# MP5x16_V1_0.net
KiCad netlist of a schematic drawn in EAGLE
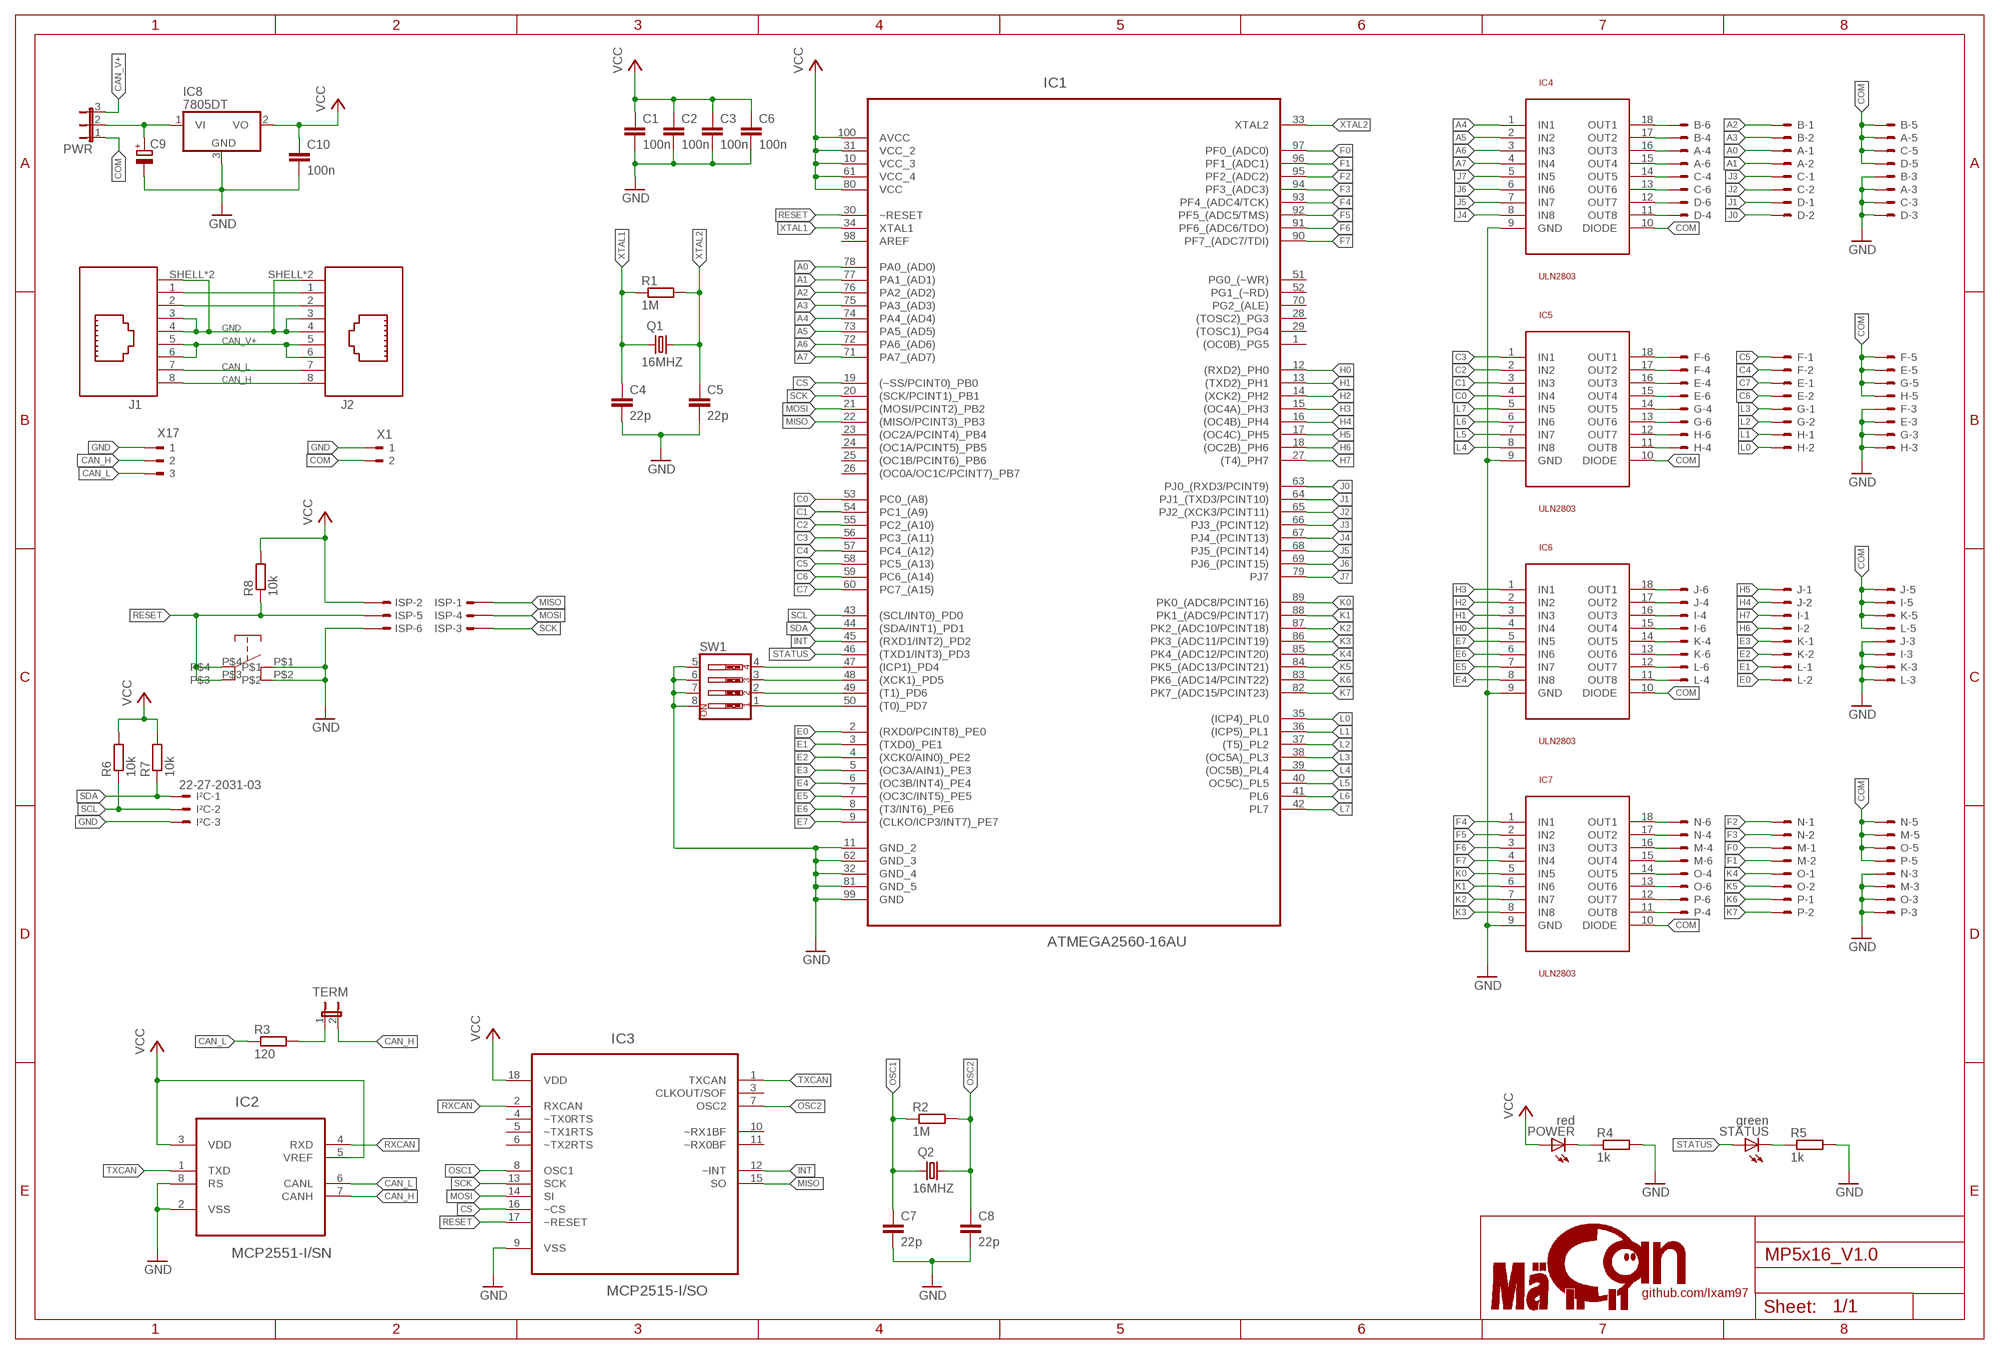
[diagram p0: schematic, sheet 1]

(export (version "E")
  (design (tool "Eeschema 10.0.6"))
  (components
    (comp (ref "A")
      (value "22-27-2061-06")
      (footprint "eagle-import:6410-06")
      (fields (field (name "MF") "MOLEX"))
      (libsource (lib "eagle-import") (part "22-?-0627-2061"))
    )
    (comp (ref "B")
      (value "22-27-2061-06")
      (footprint "eagle-import:6410-06")
      (fields (field (name "MF") "MOLEX"))
      (libsource (lib "eagle-import") (part "22-?-0627-2061"))
    )
    (comp (ref "C")
      (value "22-27-2061-06")
      (footprint "eagle-import:6410-06")
      (fields (field (name "MF") "MOLEX"))
      (libsource (lib "eagle-import") (part "22-?-0627-2061"))
    )
    (comp (ref "C1")
      (value "100n")
      (footprint "eagle-import:C0402")
      (libsource (lib "eagle-import") (part "C-EUC0402"))
    )
    (comp (ref "C2")
      (value "100n")
      (footprint "eagle-import:C0402")
      (libsource (lib "eagle-import") (part "C-EUC0402"))
    )
    (comp (ref "C3")
      (value "100n")
      (footprint "eagle-import:C0402")
      (libsource (lib "eagle-import") (part "C-EUC0402"))
    )
    (comp (ref "C4")
      (value "22p")
      (footprint "eagle-import:C0402")
      (libsource (lib "eagle-import") (part "C-EUC0402"))
    )
    (comp (ref "C5")
      (value "22p")
      (footprint "eagle-import:C0402")
      (libsource (lib "eagle-import") (part "C-EUC0402"))
    )
    (comp (ref "C6")
      (value "100n")
      (footprint "eagle-import:C0402")
      (libsource (lib "eagle-import") (part "C-EUC0402"))
    )
    (comp (ref "C7")
      (value "22p")
      (footprint "eagle-import:C0402")
      (libsource (lib "eagle-import") (part "C-EUC0402"))
    )
    (comp (ref "C8")
      (value "22p")
      (footprint "eagle-import:C0402")
      (libsource (lib "eagle-import") (part "C-EUC0402"))
    )
    (comp (ref "C9")
      (value "CPOL-EUCT3216")
      (footprint "eagle-import:CT3216")
      (libsource (lib "eagle-import") (part "CPOL-EUCT3216"))
    )
    (comp (ref "C10")
      (value "100n")
      (footprint "eagle-import:C0402")
      (libsource (lib "eagle-import") (part "C-EUC0402"))
    )
    (comp (ref "D")
      (value "22-27-2061-06")
      (footprint "eagle-import:6410-06")
      (fields (field (name "MF") "MOLEX"))
      (libsource (lib "eagle-import") (part "22-?-0627-2061"))
    )
    (comp (ref "E")
      (value "22-27-2061-06")
      (footprint "eagle-import:6410-06")
      (fields (field (name "MF") "MOLEX"))
      (libsource (lib "eagle-import") (part "22-?-0627-2061"))
    )
    (comp (ref "F")
      (value "22-27-2061-06")
      (footprint "eagle-import:6410-06")
      (fields (field (name "MF") "MOLEX"))
      (libsource (lib "eagle-import") (part "22-?-0627-2061"))
    )
    (comp (ref "G")
      (value "22-27-2061-06")
      (footprint "eagle-import:6410-06")
      (fields (field (name "MF") "MOLEX"))
      (libsource (lib "eagle-import") (part "22-?-0627-2061"))
    )
    (comp (ref "H")
      (value "22-27-2061-06")
      (footprint "eagle-import:6410-06")
      (fields (field (name "MF") "MOLEX"))
      (libsource (lib "eagle-import") (part "22-?-0627-2061"))
    )
    (comp (ref "I")
      (value "22-27-2061-06")
      (footprint "eagle-import:6410-06")
      (fields (field (name "MF") "MOLEX"))
      (libsource (lib "eagle-import") (part "22-?-0627-2061"))
    )
    (comp (ref "IC1")
      (value "ATMEGA2560-16AU")
      (footprint "eagle-import:QFP50P1600X1600X120-100N")
      (fields (field (name "MF") "Microchip"))
      (libsource (lib "eagle-import") (part "ATMEGA2560-16AU"))
    )
    (comp (ref "IC2")
      (value "MCP2551-I/SN")
      (footprint "eagle-import:SOIC127P600X175-8N")
      (libsource (lib "eagle-import") (part "MCP2551-I/SN"))
    )
    (comp (ref "IC3")
      (value "MCP2515-I/SO")
      (footprint "eagle-import:SOIC127P1034X264-18N")
      (libsource (lib "eagle-import") (part "MCP2515-I/SO"))
    )
    (comp (ref "IC4")
      (value "ULN2803")
      (footprint "eagle-import:SO18L")
      (libsource (lib "eagle-import") (part "ULN2803"))
    )
    (comp (ref "IC5")
      (value "ULN2803")
      (footprint "eagle-import:SO18L")
      (libsource (lib "eagle-import") (part "ULN2803"))
    )
    (comp (ref "IC6")
      (value "ULN2803")
      (footprint "eagle-import:SO18L")
      (libsource (lib "eagle-import") (part "ULN2803"))
    )
    (comp (ref "IC7")
      (value "ULN2803")
      (footprint "eagle-import:SO18L")
      (libsource (lib "eagle-import") (part "ULN2803"))
    )
    (comp (ref "IC8")
      (value "7805DT")
      (footprint "eagle-import:TO252")
      (libsource (lib "eagle-import") (part "78DT05"))
    )
    (comp (ref "ISP")
      (value "057-006-1")
      (footprint "eagle-import:057-006-1")
      (libsource (lib "eagle-import") (part "057-006-1"))
    )
    (comp (ref "I²C")
      (value "22-27-2031-03")
      (footprint "eagle-import:6410-03")
      (fields (field (name "MF") "MOLEX"))
      (libsource (lib "eagle-import") (part "22-?-0327-2031"))
    )
    (comp (ref "J")
      (value "22-27-2061-06")
      (footprint "eagle-import:6410-06")
      (fields (field (name "MF") "MOLEX"))
      (libsource (lib "eagle-import") (part "22-?-0627-2061"))
    )
    (comp (ref "J1")
      (value "615008140421")
      (footprint "eagle-import:615008140421")
      (libsource (lib "eagle-import") (part "615008140421"))
    )
    (comp (ref "J2")
      (value "615008140421")
      (footprint "eagle-import:615008140421")
      (libsource (lib "eagle-import") (part "615008140421"))
    )
    (comp (ref "K")
      (value "22-27-2061-06")
      (footprint "eagle-import:6410-06")
      (fields (field (name "MF") "MOLEX"))
      (libsource (lib "eagle-import") (part "22-?-0627-2061"))
    )
    (comp (ref "L")
      (value "22-27-2061-06")
      (footprint "eagle-import:6410-06")
      (fields (field (name "MF") "MOLEX"))
      (libsource (lib "eagle-import") (part "22-?-0627-2061"))
    )
    (comp (ref "M")
      (value "22-27-2061-06")
      (footprint "eagle-import:6410-06")
      (fields (field (name "MF") "MOLEX"))
      (libsource (lib "eagle-import") (part "22-?-0627-2061"))
    )
    (comp (ref "N")
      (value "22-27-2061-06")
      (footprint "eagle-import:6410-06")
      (fields (field (name "MF") "MOLEX"))
      (libsource (lib "eagle-import") (part "22-?-0627-2061"))
    )
    (comp (ref "O")
      (value "22-27-2061-06")
      (footprint "eagle-import:6410-06")
      (fields (field (name "MF") "MOLEX"))
      (libsource (lib "eagle-import") (part "22-?-0627-2061"))
    )
    (comp (ref "P")
      (value "22-27-2061-06")
      (footprint "eagle-import:6410-06")
      (fields (field (name "MF") "MOLEX"))
      (libsource (lib "eagle-import") (part "22-?-0627-2061"))
    )
    (comp (ref "POWER")
      (value "red")
      (footprint "eagle-import:CHIP-LED0805")
      (libsource (lib "eagle-import") (part "LEDCHIP-LED0805"))
    )
    (comp (ref "PWR")
      (value "JP2E")
      (footprint "eagle-import:JP2")
      (libsource (lib "eagle-import") (part "JP2E"))
    )
    (comp (ref "Q1")
      (value "16MHZ")
      (footprint "eagle-import:3.2X2.5_KX-7")
      (libsource (lib "eagle-import") (part "KX-7"))
    )
    (comp (ref "Q2")
      (value "16MHZ")
      (footprint "eagle-import:3.2X2.5_KX-7")
      (libsource (lib "eagle-import") (part "KX-7"))
    )
    (comp (ref "R1")
      (value "1M")
      (footprint "eagle-import:R0402")
      (libsource (lib "eagle-import") (part "R-EU_R0402"))
    )
    (comp (ref "R2")
      (value "1M")
      (footprint "eagle-import:R0402")
      (libsource (lib "eagle-import") (part "R-EU_R0402"))
    )
    (comp (ref "R3")
      (value "120")
      (footprint "eagle-import:R0402")
      (libsource (lib "eagle-import") (part "R-EU_R0402"))
    )
    (comp (ref "R4")
      (value "1k")
      (footprint "eagle-import:R0402")
      (libsource (lib "eagle-import") (part "R-EU_R0402"))
    )
    (comp (ref "R5")
      (value "1k")
      (footprint "eagle-import:R0402")
      (libsource (lib "eagle-import") (part "R-EU_R0402"))
    )
    (comp (ref "R6")
      (value "10k")
      (footprint "eagle-import:R0402")
      (libsource (lib "eagle-import") (part "R-EU_R0402"))
    )
    (comp (ref "R7")
      (value "10k")
      (footprint "eagle-import:R0402")
      (libsource (lib "eagle-import") (part "R-EU_R0402"))
    )
    (comp (ref "R8")
      (value "10k")
      (footprint "eagle-import:R0402")
      (libsource (lib "eagle-import") (part "R-EU_R0402"))
    )
    (comp (ref "STATUS")
      (value "green")
      (footprint "eagle-import:CHIP-LED0805")
      (libsource (lib "eagle-import") (part "LEDCHIP-LED0805"))
    )
    (comp (ref "SW1")
      (value "SW_DIP-4")
      (footprint "eagle-import:EDG-04")
      (libsource (lib "eagle-import") (part "SW_DIP-4"))
    )
    (comp (ref "TERM")
      (value "JP1E")
      (footprint "eagle-import:JP1")
      (libsource (lib "eagle-import") (part "JP1E"))
    )
    (comp (ref "U$1")
      (value "LOGO")
      (footprint "eagle-import:LOGO")
      (libsource (lib "eagle-import") (part "LOGO"))
    )
    (comp (ref "U$15")
      (value "BUTTON_JLC")
      (footprint "eagle-import:BUTTON")
      (libsource (lib "eagle-import") (part "BUTTON_JLC"))
    )
    (comp (ref "X1")
      (value "180-2")
      (footprint "eagle-import:180-2")
      (libsource (lib "eagle-import") (part "180-2"))
    )
    (comp (ref "X17")
      (value "180-3")
      (footprint "eagle-import:180-3")
      (libsource (lib "eagle-import") (part "180-3"))
    )
  )
  (nets
    (net (code "1") (name "A0") (class "Default")
      (node (ref "A") (pin "1") (pinfunction "S_1") (pintype "passive"))
      (node (ref "IC1") (pin "78") (pinfunction "PA0_(AD0)_78") (pintype "bidirectional"))
    )
    (net (code "2") (name "A1") (class "Default")
      (node (ref "A") (pin "2") (pinfunction "S_2") (pintype "passive"))
      (node (ref "IC1") (pin "77") (pinfunction "PA1_(AD1)_77") (pintype "bidirectional"))
    )
    (net (code "3") (name "A2") (class "Default")
      (node (ref "B") (pin "1") (pinfunction "S_1") (pintype "passive"))
      (node (ref "IC1") (pin "76") (pinfunction "PA2_(AD2)_76") (pintype "bidirectional"))
    )
    (net (code "4") (name "A3") (class "Default")
      (node (ref "B") (pin "2") (pinfunction "S_2") (pintype "passive"))
      (node (ref "IC1") (pin "75") (pinfunction "PA3_(AD3)_75") (pintype "bidirectional"))
    )
    (net (code "5") (name "A4") (class "Default")
      (node (ref "IC1") (pin "74") (pinfunction "PA4_(AD4)_74") (pintype "bidirectional"))
      (node (ref "IC4") (pin "1") (pinfunction "IN1_1") (pintype "input"))
    )
    (net (code "6") (name "A5") (class "Default")
      (node (ref "IC1") (pin "73") (pinfunction "PA5_(AD5)_73") (pintype "bidirectional"))
      (node (ref "IC4") (pin "2") (pinfunction "IN2_2") (pintype "input"))
    )
    (net (code "7") (name "A6") (class "Default")
      (node (ref "IC1") (pin "72") (pinfunction "PA6_(AD6)_72") (pintype "bidirectional"))
      (node (ref "IC4") (pin "3") (pinfunction "IN3_3") (pintype "input"))
    )
    (net (code "8") (name "A7") (class "Default")
      (node (ref "IC1") (pin "71") (pinfunction "PA7_(AD7)_71") (pintype "bidirectional"))
      (node (ref "IC4") (pin "4") (pinfunction "IN4_4") (pintype "input"))
    )
    (net (code "9") (name "C0") (class "Default")
      (node (ref "IC1") (pin "53") (pinfunction "PC0_(A8)_53") (pintype "bidirectional"))
      (node (ref "IC5") (pin "4") (pinfunction "IN4_4") (pintype "input"))
    )
    (net (code "10") (name "C1") (class "Default")
      (node (ref "IC1") (pin "54") (pinfunction "PC1_(A9)_54") (pintype "bidirectional"))
      (node (ref "IC5") (pin "3") (pinfunction "IN3_3") (pintype "input"))
    )
    (net (code "11") (name "C2") (class "Default")
      (node (ref "IC1") (pin "55") (pinfunction "PC2_(A10)_55") (pintype "bidirectional"))
      (node (ref "IC5") (pin "2") (pinfunction "IN2_2") (pintype "input"))
    )
    (net (code "12") (name "C3") (class "Default")
      (node (ref "IC1") (pin "56") (pinfunction "PC3_(A11)_56") (pintype "bidirectional"))
      (node (ref "IC5") (pin "1") (pinfunction "IN1_1") (pintype "input"))
    )
    (net (code "13") (name "C4") (class "Default")
      (node (ref "F") (pin "2") (pinfunction "S_2") (pintype "passive"))
      (node (ref "IC1") (pin "57") (pinfunction "PC4_(A12)_57") (pintype "bidirectional"))
    )
    (net (code "14") (name "C5") (class "Default")
      (node (ref "F") (pin "1") (pinfunction "S_1") (pintype "passive"))
      (node (ref "IC1") (pin "58") (pinfunction "PC5_(A13)_58") (pintype "bidirectional"))
    )
    (net (code "15") (name "C6") (class "Default")
      (node (ref "E") (pin "2") (pinfunction "S_2") (pintype "passive"))
      (node (ref "IC1") (pin "59") (pinfunction "PC6_(A14)_59") (pintype "bidirectional"))
    )
    (net (code "16") (name "C7") (class "Default")
      (node (ref "E") (pin "1") (pinfunction "S_1") (pintype "passive"))
      (node (ref "IC1") (pin "60") (pinfunction "PC7_(A15)_60") (pintype "bidirectional"))
    )
    (net (code "17") (name "CAN_H") (class "Default")
      (node (ref "IC2") (pin "7") (pinfunction "CANH_7") (pintype "bidirectional"))
      (node (ref "J1") (pin "8") (pinfunction "8_8") (pintype "passive"))
      (node (ref "J2") (pin "8") (pinfunction "8_8") (pintype "passive"))
      (node (ref "TERM") (pin "2") (pinfunction "2_2") (pintype "passive"))
      (node (ref "X17") (pin "2") (pinfunction "2_2") (pintype "passive"))
    )
    (net (code "18") (name "CAN_L") (class "Default")
      (node (ref "IC2") (pin "6") (pinfunction "CANL_6") (pintype "bidirectional"))
      (node (ref "J1") (pin "7") (pinfunction "7_7") (pintype "passive"))
      (node (ref "J2") (pin "7") (pinfunction "7_7") (pintype "passive"))
      (node (ref "R3") (pin "1") (pinfunction "1_1") (pintype "passive"))
      (node (ref "X17") (pin "3") (pinfunction "3_3") (pintype "passive"))
    )
    (net (code "19") (name "CAN_V+") (class "Default")
      (node (ref "J1") (pin "5") (pinfunction "5_5") (pintype "passive"))
      (node (ref "J1") (pin "6") (pinfunction "6_6") (pintype "passive"))
      (node (ref "J2") (pin "5") (pinfunction "5_5") (pintype "passive"))
      (node (ref "J2") (pin "6") (pinfunction "6_6") (pintype "passive"))
      (node (ref "PWR") (pin "3") (pinfunction "3_3") (pintype "passive"))
    )
    (net (code "20") (name "COM") (class "Default")
      (node (ref "A") (pin "5") (pinfunction "S_5") (pintype "passive"))
      (node (ref "B") (pin "5") (pinfunction "S_5") (pintype "passive"))
      (node (ref "C") (pin "5") (pinfunction "S_5") (pintype "passive"))
      (node (ref "D") (pin "5") (pinfunction "S_5") (pintype "passive"))
      (node (ref "E") (pin "5") (pinfunction "S_5") (pintype "passive"))
      (node (ref "F") (pin "5") (pinfunction "S_5") (pintype "passive"))
      (node (ref "G") (pin "5") (pinfunction "S_5") (pintype "passive"))
      (node (ref "H") (pin "5") (pinfunction "S_5") (pintype "passive"))
      (node (ref "I") (pin "5") (pinfunction "S_5") (pintype "passive"))
      (node (ref "IC4") (pin "10") (pinfunction "DIODE_10") (pintype "power_in"))
      (node (ref "IC5") (pin "10") (pinfunction "DIODE_10") (pintype "power_in"))
      (node (ref "IC6") (pin "10") (pinfunction "DIODE_10") (pintype "power_in"))
      (node (ref "IC7") (pin "10") (pinfunction "DIODE_10") (pintype "power_in"))
      (node (ref "J") (pin "5") (pinfunction "S_5") (pintype "passive"))
      (node (ref "K") (pin "5") (pinfunction "S_5") (pintype "passive"))
      (node (ref "L") (pin "5") (pinfunction "S_5") (pintype "passive"))
      (node (ref "M") (pin "5") (pinfunction "S_5") (pintype "passive"))
      (node (ref "N") (pin "5") (pinfunction "S_5") (pintype "passive"))
      (node (ref "O") (pin "5") (pinfunction "S_5") (pintype "passive"))
      (node (ref "P") (pin "5") (pinfunction "S_5") (pintype "passive"))
      (node (ref "PWR") (pin "1") (pinfunction "1_1") (pintype "passive"))
      (node (ref "X1") (pin "2") (pinfunction "2_2") (pintype "passive"))
    )
    (net (code "21") (name "CS") (class "Default")
      (node (ref "IC1") (pin "19") (pinfunction "(~{SS/PCINT0})_PB0_19") (pintype "bidirectional"))
      (node (ref "IC3") (pin "16") (pinfunction "~{CS}_16") (pintype "input"))
    )
    (net (code "22") (name "E0") (class "Default")
      (node (ref "IC1") (pin "2") (pinfunction "(RXD0/PCINT8)_PE0_2") (pintype "bidirectional"))
      (node (ref "L") (pin "2") (pinfunction "S_2") (pintype "passive"))
    )
    (net (code "23") (name "E1") (class "Default")
      (node (ref "IC1") (pin "3") (pinfunction "(TXD0)_PE1_3") (pintype "bidirectional"))
      (node (ref "L") (pin "1") (pinfunction "S_1") (pintype "passive"))
    )
    (net (code "24") (name "E2") (class "Default")
      (node (ref "IC1") (pin "4") (pinfunction "(XCK0/AIN0)_PE2_4") (pintype "bidirectional"))
      (node (ref "K") (pin "2") (pinfunction "S_2") (pintype "passive"))
    )
    (net (code "25") (name "E3") (class "Default")
      (node (ref "IC1") (pin "5") (pinfunction "(OC3A/AIN1)_PE3_5") (pintype "bidirectional"))
      (node (ref "K") (pin "1") (pinfunction "S_1") (pintype "passive"))
    )
    (net (code "26") (name "E4") (class "Default")
      (node (ref "IC1") (pin "6") (pinfunction "(OC3B/INT4)_PE4_6") (pintype "bidirectional"))
      (node (ref "IC6") (pin "8") (pinfunction "IN8_8") (pintype "input"))
    )
    (net (code "27") (name "E5") (class "Default")
      (node (ref "IC1") (pin "7") (pinfunction "(OC3C/INT5)_PE5_7") (pintype "bidirectional"))
      (node (ref "IC6") (pin "7") (pinfunction "IN7_7") (pintype "input"))
    )
    (net (code "28") (name "E6") (class "Default")
      (node (ref "IC1") (pin "8") (pinfunction "(T3/INT6)_PE6_8") (pintype "bidirectional"))
      (node (ref "IC6") (pin "6") (pinfunction "IN6_6") (pintype "input"))
    )
    (net (code "29") (name "E7") (class "Default")
      (node (ref "IC1") (pin "9") (pinfunction "(CLKO/ICP3/INT7)_PE7_9") (pintype "bidirectional"))
      (node (ref "IC6") (pin "5") (pinfunction "IN5_5") (pintype "input"))
    )
    (net (code "30") (name "F0") (class "Default")
      (node (ref "IC1") (pin "97") (pinfunction "PF0_(ADC0)_97") (pintype "bidirectional"))
      (node (ref "M") (pin "1") (pinfunction "S_1") (pintype "passive"))
    )
    (net (code "31") (name "F1") (class "Default")
      (node (ref "IC1") (pin "96") (pinfunction "PF1_(ADC1)_96") (pintype "bidirectional"))
      (node (ref "M") (pin "2") (pinfunction "S_2") (pintype "passive"))
    )
    (net (code "32") (name "F2") (class "Default")
      (node (ref "IC1") (pin "95") (pinfunction "PF2_(ADC2)_95") (pintype "bidirectional"))
      (node (ref "N") (pin "1") (pinfunction "S_1") (pintype "passive"))
    )
    (net (code "33") (name "F3") (class "Default")
      (node (ref "IC1") (pin "94") (pinfunction "PF3_(ADC3)_94") (pintype "bidirectional"))
      (node (ref "N") (pin "2") (pinfunction "S_2") (pintype "passive"))
    )
    (net (code "34") (name "F4") (class "Default")
      (node (ref "IC1") (pin "93") (pinfunction "PF4_(ADC4/TCK)_93") (pintype "bidirectional"))
      (node (ref "IC7") (pin "1") (pinfunction "IN1_1") (pintype "input"))
    )
    (net (code "35") (name "F5") (class "Default")
      (node (ref "IC1") (pin "92") (pinfunction "PF5_(ADC5/TMS)_92") (pintype "bidirectional"))
      (node (ref "IC7") (pin "2") (pinfunction "IN2_2") (pintype "input"))
    )
    (net (code "36") (name "F6") (class "Default")
      (node (ref "IC1") (pin "91") (pinfunction "PF6_(ADC6/TDO)_91") (pintype "bidirectional"))
      (node (ref "IC7") (pin "3") (pinfunction "IN3_3") (pintype "input"))
    )
    (net (code "37") (name "F7") (class "Default")
      (node (ref "IC1") (pin "90") (pinfunction "PF7_(ADC7/TDI)_90") (pintype "bidirectional"))
      (node (ref "IC7") (pin "4") (pinfunction "IN4_4") (pintype "input"))
    )
    (net (code "38") (name "GND") (class "Default")
      (node (ref "A") (pin "3") (pinfunction "S_3") (pintype "passive"))
      (node (ref "B") (pin "3") (pinfunction "S_3") (pintype "passive"))
      (node (ref "C") (pin "3") (pinfunction "S_3") (pintype "passive"))
      (node (ref "C1") (pin "2") (pinfunction "2_2") (pintype "passive"))
      (node (ref "C10") (pin "2") (pinfunction "2_2") (pintype "passive"))
      (node (ref "C2") (pin "2") (pinfunction "2_2") (pintype "passive"))
      (node (ref "C3") (pin "2") (pinfunction "2_2") (pintype "passive"))
      (node (ref "C4") (pin "2") (pinfunction "2_2") (pintype "passive"))
      (node (ref "C5") (pin "2") (pinfunction "2_2") (pintype "passive"))
      (node (ref "C6") (pin "2") (pinfunction "2_2") (pintype "passive"))
      (node (ref "C7") (pin "2") (pinfunction "2_2") (pintype "passive"))
      (node (ref "C8") (pin "2") (pinfunction "2_2") (pintype "passive"))
      (node (ref "C9") (pin "-") (pinfunction "-_-") (pintype "passive"))
      (node (ref "D") (pin "3") (pinfunction "S_3") (pintype "passive"))
      (node (ref "E") (pin "3") (pinfunction "S_3") (pintype "passive"))
      (node (ref "F") (pin "3") (pinfunction "S_3") (pintype "passive"))
      (node (ref "G") (pin "3") (pinfunction "S_3") (pintype "passive"))
      (node (ref "H") (pin "3") (pinfunction "S_3") (pintype "passive"))
      (node (ref "I") (pin "3") (pinfunction "S_3") (pintype "passive"))
      (node (ref "IC1") (pin "11") (pinfunction "GND_2_11") (pintype "passive"))
      (node (ref "IC1") (pin "32") (pinfunction "GND_4_32") (pintype "passive"))
      (node (ref "IC1") (pin "62") (pinfunction "GND_3_62") (pintype "passive"))
      (node (ref "IC1") (pin "81") (pinfunction "GND_5_81") (pintype "passive"))
      (node (ref "IC1") (pin "99") (pinfunction "GND_99") (pintype "passive"))
      (node (ref "IC2") (pin "2") (pinfunction "VSS_2") (pintype "passive"))
      (node (ref "IC2") (pin "8") (pinfunction "RS_8") (pintype "input"))
      (node (ref "IC3") (pin "9") (pinfunction "VSS_9") (pintype "power_in"))
      (node (ref "IC4") (pin "9") (pinfunction "GND_9") (pintype "power_in"))
      (node (ref "IC5") (pin "9") (pinfunction "GND_9") (pintype "power_in"))
      (node (ref "IC6") (pin "9") (pinfunction "GND_9") (pintype "power_in"))
      (node (ref "IC7") (pin "9") (pinfunction "GND_9") (pintype "power_in"))
      (node (ref "IC8") (pin "3") (pinfunction "GND_3") (pintype "passive"))
      (node (ref "ISP") (pin "6") (pinfunction "S_6") (pintype "passive"))
      (node (ref "I²C") (pin "3") (pinfunction "S_3") (pintype "passive"))
      (node (ref "J") (pin "3") (pinfunction "S_3") (pintype "passive"))
      (node (ref "J1") (pin "3") (pinfunction "3_3") (pintype "passive"))
      (node (ref "J1") (pin "4") (pinfunction "4_4") (pintype "passive"))
      (node (ref "J1") (pin "SHELL") (pinfunction "SHIELD_SHELL") (pintype "passive"))
      (node (ref "J1") (pin "SHELL1") (pinfunction "SHIELD_SHELL1") (pintype "passive"))
      (node (ref "J2") (pin "3") (pinfunction "3_3") (pintype "passive"))
      (node (ref "J2") (pin "4") (pinfunction "4_4") (pintype "passive"))
      (node (ref "J2") (pin "SHELL") (pinfunction "SHIELD_SHELL") (pintype "passive"))
      (node (ref "J2") (pin "SHELL1") (pinfunction "SHIELD_SHELL1") (pintype "passive"))
      (node (ref "K") (pin "3") (pinfunction "S_3") (pintype "passive"))
      (node (ref "L") (pin "3") (pinfunction "S_3") (pintype "passive"))
      (node (ref "M") (pin "3") (pinfunction "S_3") (pintype "passive"))
      (node (ref "N") (pin "3") (pinfunction "S_3") (pintype "passive"))
      (node (ref "O") (pin "3") (pinfunction "S_3") (pintype "passive"))
      (node (ref "P") (pin "3") (pinfunction "S_3") (pintype "passive"))
      (node (ref "R4") (pin "2") (pinfunction "2_2") (pintype "passive"))
      (node (ref "R5") (pin "2") (pinfunction "2_2") (pintype "passive"))
      (node (ref "SW1") (pin "5") (pinfunction "5_5") (pintype "passive"))
      (node (ref "SW1") (pin "6") (pinfunction "6_6") (pintype "passive"))
      (node (ref "SW1") (pin "7") (pinfunction "7_7") (pintype "passive"))
      (node (ref "SW1") (pin "8") (pinfunction "8_8") (pintype "passive"))
      (node (ref "U$15") (pin "P$1") (pinfunction "P$1_P$1") (pintype "bidirectional"))
      (node (ref "U$15") (pin "P$2") (pinfunction "P$2_P$2") (pintype "bidirectional"))
      (node (ref "X1") (pin "1") (pinfunction "1_1") (pintype "passive"))
      (node (ref "X17") (pin "1") (pinfunction "1_1") (pintype "passive"))
    )
    (net (code "39") (name "H0") (class "Default")
      (node (ref "IC1") (pin "12") (pinfunction "(RXD2)_PH0_12") (pintype "bidirectional"))
      (node (ref "IC6") (pin "4") (pinfunction "IN4_4") (pintype "input"))
    )
    (net (code "40") (name "H1") (class "Default")
      (node (ref "IC1") (pin "13") (pinfunction "(TXD2)_PH1_13") (pintype "bidirectional"))
      (node (ref "IC6") (pin "3") (pinfunction "IN3_3") (pintype "input"))
    )
    (net (code "41") (name "H2") (class "Default")
      (node (ref "IC1") (pin "14") (pinfunction "(XCK2)_PH2_14") (pintype "bidirectional"))
      (node (ref "IC6") (pin "2") (pinfunction "IN2_2") (pintype "input"))
    )
    (net (code "42") (name "H3") (class "Default")
      (node (ref "IC1") (pin "15") (pinfunction "(OC4A)_PH3_15") (pintype "bidirectional"))
      (node (ref "IC6") (pin "1") (pinfunction "IN1_1") (pintype "input"))
    )
    (net (code "43") (name "H4") (class "Default")
      (node (ref "IC1") (pin "16") (pinfunction "(OC4B)_PH4_16") (pintype "bidirectional"))
      (node (ref "J") (pin "2") (pinfunction "S_2") (pintype "passive"))
    )
    (net (code "44") (name "H5") (class "Default")
      (node (ref "IC1") (pin "17") (pinfunction "(OC4C)_PH5_17") (pintype "bidirectional"))
      (node (ref "J") (pin "1") (pinfunction "S_1") (pintype "passive"))
    )
    (net (code "45") (name "H6") (class "Default")
      (node (ref "I") (pin "2") (pinfunction "S_2") (pintype "passive"))
      (node (ref "IC1") (pin "18") (pinfunction "(OC2B)_PH6_18") (pintype "bidirectional"))
    )
    (net (code "46") (name "H7") (class "Default")
      (node (ref "I") (pin "1") (pinfunction "S_1") (pintype "passive"))
      (node (ref "IC1") (pin "27") (pinfunction "(T4)_PH7_27") (pintype "bidirectional"))
    )
    (net (code "47") (name "INT") (class "Default")
      (node (ref "IC1") (pin "45") (pinfunction "(RXD1/INT2)_PD2_45") (pintype "bidirectional"))
      (node (ref "IC3") (pin "12") (pinfunction "~{INT}_12") (pintype "output"))
    )
    (net (code "48") (name "J0") (class "Default")
      (node (ref "D") (pin "2") (pinfunction "S_2") (pintype "passive"))
      (node (ref "IC1") (pin "63") (pinfunction "PJ0_(RXD3/PCINT9)_63") (pintype "bidirectional"))
    )
    (net (code "49") (name "J1") (class "Default")
      (node (ref "D") (pin "1") (pinfunction "S_1") (pintype "passive"))
      (node (ref "IC1") (pin "64") (pinfunction "PJ1_(TXD3/PCINT10)_64") (pintype "bidirectional"))
    )
    (net (code "50") (name "J2") (class "Default")
      (node (ref "C") (pin "2") (pinfunction "S_2") (pintype "passive"))
      (node (ref "IC1") (pin "65") (pinfunction "PJ2_(XCK3/PCINT11)_65") (pintype "bidirectional"))
    )
    (net (code "51") (name "J3") (class "Default")
      (node (ref "C") (pin "1") (pinfunction "S_1") (pintype "passive"))
      (node (ref "IC1") (pin "66") (pinfunction "PJ3_(PCINT12)_66") (pintype "bidirectional"))
    )
    (net (code "52") (name "J4") (class "Default")
      (node (ref "IC1") (pin "67") (pinfunction "PJ4_(PCINT13)_67") (pintype "bidirectional"))
      (node (ref "IC4") (pin "8") (pinfunction "IN8_8") (pintype "input"))
    )
    (net (code "53") (name "J5") (class "Default")
      (node (ref "IC1") (pin "68") (pinfunction "PJ5_(PCINT14)_68") (pintype "bidirectional"))
      (node (ref "IC4") (pin "7") (pinfunction "IN7_7") (pintype "input"))
    )
    (net (code "54") (name "J6") (class "Default")
      (node (ref "IC1") (pin "69") (pinfunction "PJ6_(PCINT15)_69") (pintype "bidirectional"))
      (node (ref "IC4") (pin "6") (pinfunction "IN6_6") (pintype "input"))
    )
    (net (code "55") (name "J7") (class "Default")
      (node (ref "IC1") (pin "79") (pinfunction "PJ7_79") (pintype "bidirectional"))
      (node (ref "IC4") (pin "5") (pinfunction "IN5_5") (pintype "input"))
    )
    (net (code "56") (name "K0") (class "Default")
      (node (ref "IC1") (pin "89") (pinfunction "PK0_(ADC8/PCINT16)_89") (pintype "bidirectional"))
      (node (ref "IC7") (pin "5") (pinfunction "IN5_5") (pintype "input"))
    )
    (net (code "57") (name "K1") (class "Default")
      (node (ref "IC1") (pin "88") (pinfunction "PK1_(ADC9/PCINT17)_88") (pintype "bidirectional"))
      (node (ref "IC7") (pin "6") (pinfunction "IN6_6") (pintype "input"))
    )
    (net (code "58") (name "K2") (class "Default")
      (node (ref "IC1") (pin "87") (pinfunction "PK2_(ADC10/PCINT18)_87") (pintype "bidirectional"))
      (node (ref "IC7") (pin "7") (pinfunction "IN7_7") (pintype "input"))
    )
    (net (code "59") (name "K3") (class "Default")
      (node (ref "IC1") (pin "86") (pinfunction "PK3_(ADC11/PCINT19)_86") (pintype "bidirectional"))
      (node (ref "IC7") (pin "8") (pinfunction "IN8_8") (pintype "input"))
    )
    (net (code "60") (name "K4") (class "Default")
      (node (ref "IC1") (pin "85") (pinfunction "PK4_(ADC12/PCINT20)_85") (pintype "bidirectional"))
      (node (ref "O") (pin "1") (pinfunction "S_1") (pintype "passive"))
    )
    (net (code "61") (name "K5") (class "Default")
      (node (ref "IC1") (pin "84") (pinfunction "PK5_(ADC13/PCINT21)_84") (pintype "bidirectional"))
      (node (ref "O") (pin "2") (pinfunction "S_2") (pintype "passive"))
    )
    (net (code "62") (name "K6") (class "Default")
      (node (ref "IC1") (pin "83") (pinfunction "PK6_(ADC14/PCINT22)_83") (pintype "bidirectional"))
      (node (ref "P") (pin "1") (pinfunction "S_1") (pintype "passive"))
    )
    (net (code "63") (name "K7") (class "Default")
      (node (ref "IC1") (pin "82") (pinfunction "PK7_(ADC15/PCINT23)_82") (pintype "bidirectional"))
      (node (ref "P") (pin "2") (pinfunction "S_2") (pintype "passive"))
    )
    (net (code "64") (name "L0") (class "Default")
      (node (ref "H") (pin "2") (pinfunction "S_2") (pintype "passive"))
      (node (ref "IC1") (pin "35") (pinfunction "(ICP4)_PL0_35") (pintype "bidirectional"))
    )
    (net (code "65") (name "L1") (class "Default")
      (node (ref "H") (pin "1") (pinfunction "S_1") (pintype "passive"))
      (node (ref "IC1") (pin "36") (pinfunction "(ICP5)_PL1_36") (pintype "bidirectional"))
    )
    (net (code "66") (name "L2") (class "Default")
      (node (ref "G") (pin "2") (pinfunction "S_2") (pintype "passive"))
      (node (ref "IC1") (pin "37") (pinfunction "(T5)_PL2_37") (pintype "bidirectional"))
    )
    (net (code "67") (name "L3") (class "Default")
      (node (ref "G") (pin "1") (pinfunction "S_1") (pintype "passive"))
      (node (ref "IC1") (pin "38") (pinfunction "(OC5A)_PL3_38") (pintype "bidirectional"))
    )
    (net (code "68") (name "L4") (class "Default")
      (node (ref "IC1") (pin "39") (pinfunction "(OC5B)_PL4_39") (pintype "bidirectional"))
      (node (ref "IC5") (pin "8") (pinfunction "IN8_8") (pintype "input"))
    )
    (net (code "69") (name "L5") (class "Default")
      (node (ref "IC1") (pin "40") (pinfunction "OC5C)_PL5_40") (pintype "bidirectional"))
      (node (ref "IC5") (pin "7") (pinfunction "IN7_7") (pintype "input"))
    )
    (net (code "70") (name "L6") (class "Default")
      (node (ref "IC1") (pin "41") (pinfunction "PL6_41") (pintype "bidirectional"))
      (node (ref "IC5") (pin "6") (pinfunction "IN6_6") (pintype "input"))
    )
    (net (code "71") (name "L7") (class "Default")
      (node (ref "IC1") (pin "42") (pinfunction "PL7_42") (pintype "bidirectional"))
      (node (ref "IC5") (pin "5") (pinfunction "IN5_5") (pintype "input"))
    )
    (net (code "72") (name "MISO") (class "Default")
      (node (ref "IC1") (pin "22") (pinfunction "(MISO/PCINT3)_PB3_22") (pintype "bidirectional"))
      (node (ref "IC3") (pin "15") (pinfunction "SO_15") (pintype "output"))
      (node (ref "ISP") (pin "1") (pinfunction "S_1") (pintype "passive"))
    )
    (net (code "73") (name "MOSI") (class "Default")
      (node (ref "IC1") (pin "21") (pinfunction "(MOSI/PCINT2)_PB2_21") (pintype "bidirectional"))
      (node (ref "IC3") (pin "14") (pinfunction "SI_14") (pintype "input"))
      (node (ref "ISP") (pin "4") (pinfunction "S_4") (pintype "passive"))
    )
    (net (code "74") (name "Net-(AD-S)") (class "Default")
      (node (ref "A") (pin "4") (pinfunction "S_4") (pintype "passive"))
      (node (ref "IC4") (pin "16") (pinfunction "OUT3_16") (pintype "open_collector"))
    )
    (net (code "75") (name "Net-(AF-S)") (class "Default")
      (node (ref "A") (pin "6") (pinfunction "S_6") (pintype "passive"))
      (node (ref "IC4") (pin "15") (pinfunction "OUT4_15") (pintype "open_collector"))
    )
    (net (code "76") (name "Net-(BD-S)") (class "Default")
      (node (ref "B") (pin "4") (pinfunction "S_4") (pintype "passive"))
      (node (ref "IC4") (pin "17") (pinfunction "OUT2_17") (pintype "open_collector"))
    )
    (net (code "77") (name "Net-(BF-S)") (class "Default")
      (node (ref "B") (pin "6") (pinfunction "S_6") (pintype "passive"))
      (node (ref "IC4") (pin "18") (pinfunction "OUT1_18") (pintype "open_collector"))
    )
    (net (code "78") (name "Net-(CD-S)") (class "Default")
      (node (ref "C") (pin "4") (pinfunction "S_4") (pintype "passive"))
      (node (ref "IC4") (pin "14") (pinfunction "OUT5_14") (pintype "open_collector"))
    )
    (net (code "79") (name "Net-(CF-S)") (class "Default")
      (node (ref "C") (pin "6") (pinfunction "S_6") (pintype "passive"))
      (node (ref "IC4") (pin "13") (pinfunction "OUT6_13") (pintype "open_collector"))
    )
    (net (code "80") (name "Net-(DD-S)") (class "Default")
      (node (ref "D") (pin "4") (pinfunction "S_4") (pintype "passive"))
      (node (ref "IC4") (pin "11") (pinfunction "OUT8_11") (pintype "open_collector"))
    )
    (net (code "81") (name "Net-(DF-S)") (class "Default")
      (node (ref "D") (pin "6") (pinfunction "S_6") (pintype "passive"))
      (node (ref "IC4") (pin "12") (pinfunction "OUT7_12") (pintype "open_collector"))
    )
    (net (code "82") (name "Net-(ED-S)") (class "Default")
      (node (ref "E") (pin "4") (pinfunction "S_4") (pintype "passive"))
      (node (ref "IC5") (pin "16") (pinfunction "OUT3_16") (pintype "open_collector"))
    )
    (net (code "83") (name "Net-(EF-S)") (class "Default")
      (node (ref "E") (pin "6") (pinfunction "S_6") (pintype "passive"))
      (node (ref "IC5") (pin "15") (pinfunction "OUT4_15") (pintype "open_collector"))
    )
    (net (code "84") (name "Net-(FD-S)") (class "Default")
      (node (ref "F") (pin "4") (pinfunction "S_4") (pintype "passive"))
      (node (ref "IC5") (pin "17") (pinfunction "OUT2_17") (pintype "open_collector"))
    )
    (net (code "85") (name "Net-(FF-S)") (class "Default")
      (node (ref "F") (pin "6") (pinfunction "S_6") (pintype "passive"))
      (node (ref "IC5") (pin "18") (pinfunction "OUT1_18") (pintype "open_collector"))
    )
    (net (code "86") (name "Net-(GD-S)") (class "Default")
      (node (ref "G") (pin "4") (pinfunction "S_4") (pintype "passive"))
      (node (ref "IC5") (pin "14") (pinfunction "OUT5_14") (pintype "open_collector"))
    )
    (net (code "87") (name "Net-(GF-S)") (class "Default")
      (node (ref "G") (pin "6") (pinfunction "S_6") (pintype "passive"))
      (node (ref "IC5") (pin "13") (pinfunction "OUT6_13") (pintype "open_collector"))
    )
    (net (code "88") (name "Net-(HD-S)") (class "Default")
      (node (ref "H") (pin "4") (pinfunction "S_4") (pintype "passive"))
      (node (ref "IC5") (pin "11") (pinfunction "OUT8_11") (pintype "open_collector"))
    )
    (net (code "89") (name "Net-(HF-S)") (class "Default")
      (node (ref "H") (pin "6") (pinfunction "S_6") (pintype "passive"))
      (node (ref "IC5") (pin "12") (pinfunction "OUT7_12") (pintype "open_collector"))
    )
    (net (code "90") (name "Net-(IC1-(ICP1)_PD4)") (class "Default")
      (node (ref "IC1") (pin "47") (pinfunction "(ICP1)_PD4_47") (pintype "bidirectional"))
      (node (ref "SW1") (pin "4") (pinfunction "4_4") (pintype "passive"))
    )
    (net (code "91") (name "Net-(IC1-(T0)_PD7)") (class "Default")
      (node (ref "IC1") (pin "50") (pinfunction "(T0)_PD7_50") (pintype "bidirectional"))
      (node (ref "SW1") (pin "1") (pinfunction "1_1") (pintype "passive"))
    )
    (net (code "92") (name "Net-(IC1-(T1)_PD6)") (class "Default")
      (node (ref "IC1") (pin "49") (pinfunction "(T1)_PD6_49") (pintype "bidirectional"))
      (node (ref "SW1") (pin "2") (pinfunction "2_2") (pintype "passive"))
    )
    (net (code "93") (name "Net-(IC1-(XCK1)_PD5)") (class "Default")
      (node (ref "IC1") (pin "48") (pinfunction "(XCK1)_PD5_48") (pintype "bidirectional"))
      (node (ref "SW1") (pin "3") (pinfunction "3_3") (pintype "passive"))
    )
    (net (code "94") (name "Net-(IC6-OUT1)") (class "Default")
      (node (ref "IC6") (pin "18") (pinfunction "OUT1_18") (pintype "open_collector"))
      (node (ref "J") (pin "6") (pinfunction "S_6") (pintype "passive"))
    )
    (net (code "95") (name "Net-(IC6-OUT2)") (class "Default")
      (node (ref "IC6") (pin "17") (pinfunction "OUT2_17") (pintype "open_collector"))
      (node (ref "J") (pin "4") (pinfunction "S_4") (pintype "passive"))
    )
    (net (code "96") (name "Net-(IC6-OUT3)") (class "Default")
      (node (ref "I") (pin "4") (pinfunction "S_4") (pintype "passive"))
      (node (ref "IC6") (pin "16") (pinfunction "OUT3_16") (pintype "open_collector"))
    )
    (net (code "97") (name "Net-(IC6-OUT4)") (class "Default")
      (node (ref "I") (pin "6") (pinfunction "S_6") (pintype "passive"))
      (node (ref "IC6") (pin "15") (pinfunction "OUT4_15") (pintype "open_collector"))
    )
    (net (code "98") (name "Net-(IC6-OUT5)") (class "Default")
      (node (ref "IC6") (pin "14") (pinfunction "OUT5_14") (pintype "open_collector"))
      (node (ref "K") (pin "4") (pinfunction "S_4") (pintype "passive"))
    )
    (net (code "99") (name "Net-(IC6-OUT6)") (class "Default")
      (node (ref "IC6") (pin "13") (pinfunction "OUT6_13") (pintype "open_collector"))
      (node (ref "K") (pin "6") (pinfunction "S_6") (pintype "passive"))
    )
    (net (code "100") (name "Net-(IC6-OUT7)") (class "Default")
      (node (ref "IC6") (pin "12") (pinfunction "OUT7_12") (pintype "open_collector"))
      (node (ref "L") (pin "6") (pinfunction "S_6") (pintype "passive"))
    )
    (net (code "101") (name "Net-(IC6-OUT8)") (class "Default")
      (node (ref "IC6") (pin "11") (pinfunction "OUT8_11") (pintype "open_collector"))
      (node (ref "L") (pin "4") (pinfunction "S_4") (pintype "passive"))
    )
    (net (code "102") (name "Net-(IC7-OUT1)") (class "Default")
      (node (ref "IC7") (pin "18") (pinfunction "OUT1_18") (pintype "open_collector"))
      (node (ref "N") (pin "6") (pinfunction "S_6") (pintype "passive"))
    )
    (net (code "103") (name "Net-(IC7-OUT2)") (class "Default")
      (node (ref "IC7") (pin "17") (pinfunction "OUT2_17") (pintype "open_collector"))
      (node (ref "N") (pin "4") (pinfunction "S_4") (pintype "passive"))
    )
    (net (code "104") (name "Net-(IC7-OUT3)") (class "Default")
      (node (ref "IC7") (pin "16") (pinfunction "OUT3_16") (pintype "open_collector"))
      (node (ref "M") (pin "4") (pinfunction "S_4") (pintype "passive"))
    )
    (net (code "105") (name "Net-(IC7-OUT4)") (class "Default")
      (node (ref "IC7") (pin "15") (pinfunction "OUT4_15") (pintype "open_collector"))
      (node (ref "M") (pin "6") (pinfunction "S_6") (pintype "passive"))
    )
    (net (code "106") (name "Net-(IC7-OUT5)") (class "Default")
      (node (ref "IC7") (pin "14") (pinfunction "OUT5_14") (pintype "open_collector"))
      (node (ref "O") (pin "4") (pinfunction "S_4") (pintype "passive"))
    )
    (net (code "107") (name "Net-(IC7-OUT6)") (class "Default")
      (node (ref "IC7") (pin "13") (pinfunction "OUT6_13") (pintype "open_collector"))
      (node (ref "O") (pin "6") (pinfunction "S_6") (pintype "passive"))
    )
    (net (code "108") (name "Net-(IC7-OUT7)") (class "Default")
      (node (ref "IC7") (pin "12") (pinfunction "OUT7_12") (pintype "open_collector"))
      (node (ref "P") (pin "6") (pinfunction "S_6") (pintype "passive"))
    )
    (net (code "109") (name "Net-(IC7-OUT8)") (class "Default")
      (node (ref "IC7") (pin "11") (pinfunction "OUT8_11") (pintype "open_collector"))
      (node (ref "P") (pin "4") (pinfunction "S_4") (pintype "passive"))
    )
    (net (code "110") (name "Net-(IC8-VI)") (class "Default")
      (node (ref "C9") (pin "+") (pinfunction "+_+") (pintype "passive"))
      (node (ref "IC8") (pin "1") (pinfunction "VI_1") (pintype "input"))
      (node (ref "PWR") (pin "2") (pinfunction "2_2") (pintype "passive"))
    )
    (net (code "111") (name "Net-(J1-Pad1)") (class "Default")
      (node (ref "J1") (pin "1") (pinfunction "1_1") (pintype "passive"))
      (node (ref "J2") (pin "1") (pinfunction "1_1") (pintype "passive"))
    )
    (net (code "112") (name "Net-(J1-Pad2)") (class "Default")
      (node (ref "J1") (pin "2") (pinfunction "2_2") (pintype "passive"))
      (node (ref "J2") (pin "2") (pinfunction "2_2") (pintype "passive"))
    )
    (net (code "113") (name "Net-(POWER-PadC)") (class "Default")
      (node (ref "POWER") (pin "C") (pinfunction "C_C") (pintype "passive"))
      (node (ref "R4") (pin "1") (pinfunction "1_1") (pintype "passive"))
    )
    (net (code "114") (name "Net-(R3-Pad2)") (class "Default")
      (node (ref "R3") (pin "2") (pinfunction "2_2") (pintype "passive"))
      (node (ref "TERM") (pin "1") (pinfunction "1_1") (pintype "passive"))
    )
    (net (code "115") (name "Net-(R5-Pad1)") (class "Default")
      (node (ref "R5") (pin "1") (pinfunction "1_1") (pintype "passive"))
      (node (ref "STATUS") (pin "C") (pinfunction "C_C") (pintype "passive"))
    )
    (net (code "116") (name "OSC1") (class "Default")
      (node (ref "C7") (pin "1") (pinfunction "1_1") (pintype "passive"))
      (node (ref "IC3") (pin "8") (pinfunction "OSC1_8") (pintype "input"))
      (node (ref "Q2") (pin "1") (pinfunction "1_1") (pintype "passive"))
      (node (ref "R2") (pin "1") (pinfunction "1_1") (pintype "passive"))
    )
    (net (code "117") (name "OSC2") (class "Default")
      (node (ref "C8") (pin "1") (pinfunction "1_1") (pintype "passive"))
      (node (ref "IC3") (pin "7") (pinfunction "OSC2_7") (pintype "output"))
      (node (ref "Q2") (pin "3") (pinfunction "2_3") (pintype "passive"))
      (node (ref "R2") (pin "2") (pinfunction "2_2") (pintype "passive"))
    )
    (net (code "118") (name "RESET") (class "Default")
      (node (ref "IC1") (pin "30") (pinfunction "~{RESET}_30") (pintype "input"))
      (node (ref "IC3") (pin "17") (pinfunction "~{RESET}_17") (pintype "input"))
      (node (ref "ISP") (pin "5") (pinfunction "S_5") (pintype "passive"))
      (node (ref "R8") (pin "1") (pinfunction "1_1") (pintype "passive"))
      (node (ref "U$15") (pin "P$3") (pinfunction "P$3_P$3") (pintype "bidirectional"))
      (node (ref "U$15") (pin "P$4") (pinfunction "P$4_P$4") (pintype "bidirectional"))
    )
    (net (code "119") (name "RXCAN") (class "Default")
      (node (ref "IC2") (pin "4") (pinfunction "RXD_4") (pintype "output"))
      (node (ref "IC3") (pin "2") (pinfunction "RXCAN_2") (pintype "input"))
    )
    (net (code "120") (name "SCK") (class "Default")
      (node (ref "IC1") (pin "20") (pinfunction "(SCK/PCINT1)_PB1_20") (pintype "bidirectional"))
      (node (ref "IC3") (pin "13") (pinfunction "SCK_13") (pintype "input"))
      (node (ref "ISP") (pin "3") (pinfunction "S_3") (pintype "passive"))
    )
    (net (code "121") (name "SCL") (class "Default")
      (node (ref "IC1") (pin "43") (pinfunction "(SCL/INT0)_PD0_43") (pintype "bidirectional"))
      (node (ref "I²C") (pin "2") (pinfunction "S_2") (pintype "passive"))
      (node (ref "R6") (pin "1") (pinfunction "1_1") (pintype "passive"))
    )
    (net (code "122") (name "SDA") (class "Default")
      (node (ref "IC1") (pin "44") (pinfunction "(SDA/INT1)_PD1_44") (pintype "bidirectional"))
      (node (ref "I²C") (pin "1") (pinfunction "S_1") (pintype "passive"))
      (node (ref "R7") (pin "1") (pinfunction "1_1") (pintype "passive"))
    )
    (net (code "123") (name "STATUS") (class "Default")
      (node (ref "IC1") (pin "46") (pinfunction "(TXD1/INT3)_PD3_46") (pintype "bidirectional"))
      (node (ref "STATUS") (pin "A") (pinfunction "A_A") (pintype "passive"))
    )
    (net (code "124") (name "TXCAN") (class "Default")
      (node (ref "IC2") (pin "1") (pinfunction "TXD_1") (pintype "input"))
      (node (ref "IC3") (pin "1") (pinfunction "TXCAN_1") (pintype "output"))
    )
    (net (code "125") (name "VCC") (class "Default")
      (node (ref "C1") (pin "1") (pinfunction "1_1") (pintype "passive"))
      (node (ref "C10") (pin "1") (pinfunction "1_1") (pintype "passive"))
      (node (ref "C2") (pin "1") (pinfunction "1_1") (pintype "passive"))
      (node (ref "C3") (pin "1") (pinfunction "1_1") (pintype "passive"))
      (node (ref "C6") (pin "1") (pinfunction "1_1") (pintype "passive"))
      (node (ref "IC1") (pin "10") (pinfunction "VCC_3_10") (pintype "power_in"))
      (node (ref "IC1") (pin "100") (pinfunction "AVCC_100") (pintype "power_in"))
      (node (ref "IC1") (pin "31") (pinfunction "VCC_2_31") (pintype "power_in"))
      (node (ref "IC1") (pin "61") (pinfunction "VCC_4_61") (pintype "power_in"))
      (node (ref "IC1") (pin "80") (pinfunction "VCC_80") (pintype "power_in"))
      (node (ref "IC2") (pin "3") (pinfunction "VDD_3") (pintype "power_in"))
      (node (ref "IC2") (pin "5") (pinfunction "VREF_5") (pintype "output"))
      (node (ref "IC3") (pin "18") (pinfunction "VDD_18") (pintype "power_in"))
      (node (ref "IC8") (pin "2") (pinfunction "VO_2") (pintype "passive"))
      (node (ref "ISP") (pin "2") (pinfunction "S_2") (pintype "passive"))
      (node (ref "POWER") (pin "A") (pinfunction "A_A") (pintype "passive"))
      (node (ref "R6") (pin "2") (pinfunction "2_2") (pintype "passive"))
      (node (ref "R7") (pin "2") (pinfunction "2_2") (pintype "passive"))
      (node (ref "R8") (pin "2") (pinfunction "2_2") (pintype "passive"))
    )
    (net (code "126") (name "XTAL1") (class "Default")
      (node (ref "C4") (pin "1") (pinfunction "1_1") (pintype "passive"))
      (node (ref "IC1") (pin "34") (pinfunction "XTAL1_34") (pintype "input"))
      (node (ref "Q1") (pin "1") (pinfunction "1_1") (pintype "passive"))
      (node (ref "R1") (pin "1") (pinfunction "1_1") (pintype "passive"))
    )
    (net (code "127") (name "XTAL2") (class "Default")
      (node (ref "C5") (pin "1") (pinfunction "1_1") (pintype "passive"))
      (node (ref "IC1") (pin "33") (pinfunction "XTAL2_33") (pintype "output"))
      (node (ref "Q1") (pin "3") (pinfunction "2_3") (pintype "passive"))
      (node (ref "R1") (pin "2") (pinfunction "2_2") (pintype "passive"))
    )
    (net (code "128") (name "unconnected-(IC1-(OC0A{slash}OC1C{slash}PCINT7)_PB7-Pad26)") (class "Default")
      (node (ref "IC1") (pin "26") (pinfunction "(OC0A/OC1C/PCINT7)_PB7_26") (pintype "bidirectional"))
    )
    (net (code "129") (name "unconnected-(IC1-(OC0B)_PG5-Pad1)") (class "Default")
      (node (ref "IC1") (pin "1") (pinfunction "(OC0B)_PG5_1") (pintype "bidirectional"))
    )
    (net (code "130") (name "unconnected-(IC1-(OC1A{slash}PCINT5)_PB5-Pad24)") (class "Default")
      (node (ref "IC1") (pin "24") (pinfunction "(OC1A/PCINT5)_PB5_24") (pintype "bidirectional"))
    )
    (net (code "131") (name "unconnected-(IC1-(OC1B{slash}PCINT6)_PB6-Pad25)") (class "Default")
      (node (ref "IC1") (pin "25") (pinfunction "(OC1B/PCINT6)_PB6_25") (pintype "bidirectional"))
    )
    (net (code "132") (name "unconnected-(IC1-(OC2A{slash}PCINT4)_PB4-Pad23)") (class "Default")
      (node (ref "IC1") (pin "23") (pinfunction "(OC2A/PCINT4)_PB4_23") (pintype "bidirectional"))
    )
    (net (code "133") (name "unconnected-(IC1-(TOSC1)_PG4-Pad29)") (class "Default")
      (node (ref "IC1") (pin "29") (pinfunction "(TOSC1)_PG4_29") (pintype "bidirectional"))
    )
    (net (code "134") (name "unconnected-(IC1-(TOSC2)_PG3-Pad28)") (class "Default")
      (node (ref "IC1") (pin "28") (pinfunction "(TOSC2)_PG3_28") (pintype "bidirectional"))
    )
    (net (code "135") (name "unconnected-(IC1-AREF-Pad98)") (class "Default")
      (node (ref "IC1") (pin "98") (pinfunction "AREF_98") (pintype "input"))
    )
    (net (code "136") (name "unconnected-(IC1-PG0_(~{WR})-Pad51)") (class "Default")
      (node (ref "IC1") (pin "51") (pinfunction "PG0_(~{WR})_51") (pintype "bidirectional"))
    )
    (net (code "137") (name "unconnected-(IC1-PG1_(~{RD})-Pad52)") (class "Default")
      (node (ref "IC1") (pin "52") (pinfunction "PG1_(~{RD})_52") (pintype "bidirectional"))
    )
    (net (code "138") (name "unconnected-(IC1-PG2_(ALE)-Pad70)") (class "Default")
      (node (ref "IC1") (pin "70") (pinfunction "PG2_(ALE)_70") (pintype "bidirectional"))
    )
    (net (code "139") (name "unconnected-(IC3-CLKOUT{slash}SOF-Pad3)") (class "Default")
      (node (ref "IC3") (pin "3") (pinfunction "CLKOUT/SOF_3") (pintype "output"))
    )
    (net (code "140") (name "unconnected-(IC3-~{RX0BF}-Pad11)") (class "Default")
      (node (ref "IC3") (pin "11") (pinfunction "~{RX0BF}_11") (pintype "output"))
    )
    (net (code "141") (name "unconnected-(IC3-~{RX1BF}-Pad10)") (class "Default")
      (node (ref "IC3") (pin "10") (pinfunction "~{RX1BF}_10") (pintype "output"))
    )
    (net (code "142") (name "unconnected-(IC3-~{TX0RTS}-Pad4)") (class "Default")
      (node (ref "IC3") (pin "4") (pinfunction "~{TX0RTS}_4") (pintype "input"))
    )
    (net (code "143") (name "unconnected-(IC3-~{TX1RTS}-Pad5)") (class "Default")
      (node (ref "IC3") (pin "5") (pinfunction "~{TX1RTS}_5") (pintype "input"))
    )
    (net (code "144") (name "unconnected-(IC3-~{TX2RTS}-Pad6)") (class "Default")
      (node (ref "IC3") (pin "6") (pinfunction "~{TX2RTS}_6") (pintype "input"))
    )
  )
)
